# Measurements.net
KiCad netlist of a schematic drawn in Altium Designer
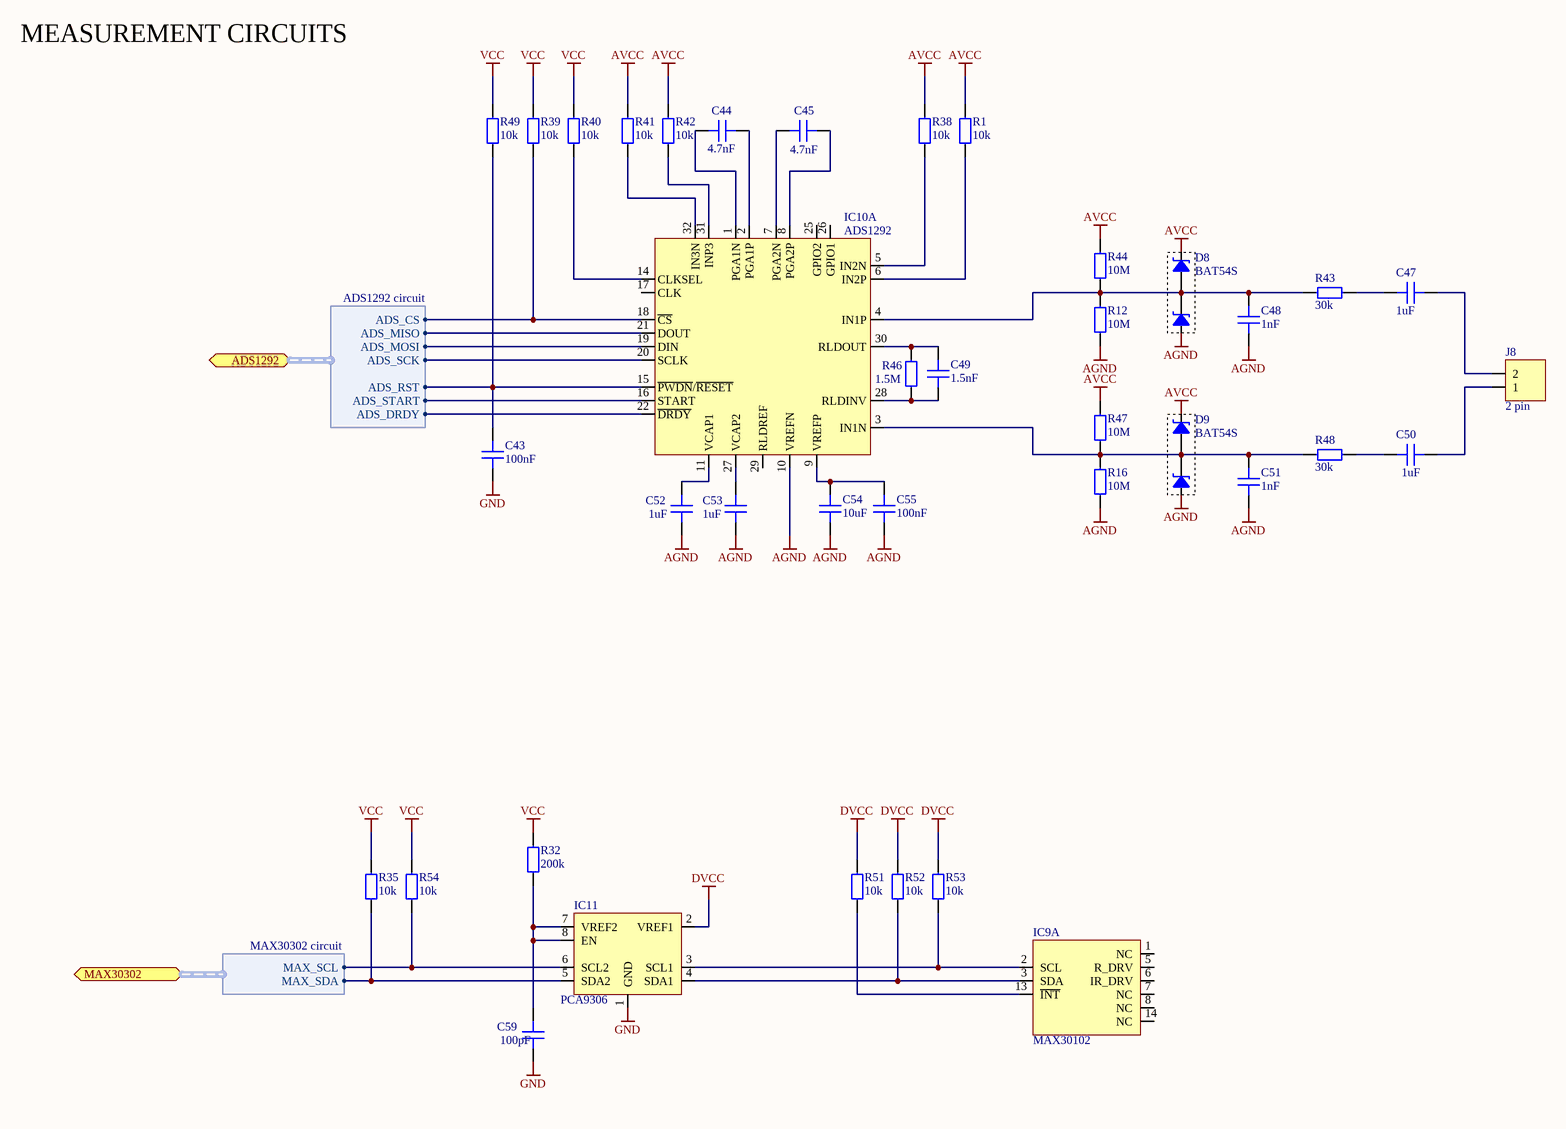
[diagram p0: Measurements.SchDoc]

(export (version "E")
  (design (tool "Eeschema 10.0.6"))
  (components
    (comp (ref "C43")
      (value "100nF")
      (footprint "CAP 0603")
      (description "SMT Capacitor")
      (libsource (lib "Passive") (part "Capacitor"))
    )
    (comp (ref "C44")
      (value "4.7nF")
      (footprint "CAP 0603")
      (description "SMT Capacitor")
      (libsource (lib "Passive") (part "Capacitor"))
    )
    (comp (ref "C45")
      (value "4.7nF")
      (footprint "CAP 0603")
      (description "SMT Capacitor")
      (libsource (lib "Passive") (part "Capacitor"))
    )
    (comp (ref "C47")
      (value "1uF")
      (footprint "CAP 0603")
      (description "SMT Capacitor")
      (libsource (lib "Passive") (part "Capacitor"))
    )
    (comp (ref "C48")
      (value "1nF")
      (footprint "CAP 0603")
      (description "SMT Capacitor")
      (libsource (lib "Passive") (part "Capacitor"))
    )
    (comp (ref "C49")
      (value "1.5nF")
      (footprint "CAP 0603")
      (description "SMT Capacitor")
      (libsource (lib "Passive") (part "Capacitor"))
    )
    (comp (ref "C50")
      (value "1uF")
      (footprint "CAP 0603")
      (description "SMT Capacitor")
      (libsource (lib "Passive") (part "Capacitor"))
    )
    (comp (ref "C51")
      (value "1nF")
      (footprint "CAP 0603")
      (description "SMT Capacitor")
      (libsource (lib "Passive") (part "Capacitor"))
    )
    (comp (ref "C52")
      (value "1uF")
      (footprint "CAP 0603")
      (description "SMT Capacitor")
      (libsource (lib "Passive") (part "Capacitor"))
    )
    (comp (ref "C53")
      (value "1uF")
      (footprint "CAP 0603")
      (description "SMT Capacitor")
      (libsource (lib "Passive") (part "Capacitor"))
    )
    (comp (ref "C54")
      (value "10uF")
      (footprint "CAP 0603")
      (description "SMT Capacitor")
      (libsource (lib "Passive") (part "Capacitor"))
    )
    (comp (ref "C55")
      (value "100nF")
      (footprint "CAP 0603")
      (description "SMT Capacitor")
      (libsource (lib "Passive") (part "Capacitor"))
    )
    (comp (ref "C59")
      (value "100pF")
      (footprint "CAP 0603")
      (description "SMT Capacitor")
      (libsource (lib "Passive") (part "Capacitor"))
    )
    (comp (ref "D8")
      (value "BAT54S")
      (footprint "SOT23")
      (description "Schottky barrier diodes")
      (libsource (lib "Diodes") (part "BAT54S"))
    )
    (comp (ref "D9")
      (value "BAT54S")
      (footprint "SOT23")
      (description "Schottky barrier diodes")
      (libsource (lib "Diodes") (part "BAT54S"))
    )
    (comp (ref "IC9")
      (value "MAX30102")
      (footprint "MAX30102")
      (description "Pulse Oximeter and Heart-Rate Sensor")
      (libsource (lib "IC") (part "MAX30102"))
    )
    (comp (ref "IC10")
      (value "ADS1292")
      (footprint "TQFP40")
      (description "ADS1292IRSMT Analog Front End - AFE Cmplt Lw Pwr Intgrtd AFE for ECG apps")
      (libsource (lib "IC") (part "ADS1292IRSMT"))
    )
    (comp (ref "IC11")
      (value "PCA9306")
      (footprint "SSOP8")
      (description "Dual Bidirectional I2C Bus and SMBus Voltage-Level Translator")
      (libsource (lib "IC") (part "PCA9306"))
    )
    (comp (ref "J8")
      (value "2 pin")
      (footprint "HDR 1x2 2.54")
      (description "2 pin header, male")
      (libsource (lib "Connectors") (part "2 pin"))
    )
    (comp (ref "R1")
      (value "10k")
      (footprint "RES 0603")
      (description "SMDResistor")
      (libsource (lib "Passive") (part "Resistor"))
    )
    (comp (ref "R12")
      (value "10M")
      (footprint "RES 0603")
      (description "SMDResistor")
      (libsource (lib "Passive") (part "Resistor"))
    )
    (comp (ref "R16")
      (value "10M")
      (footprint "RES 0603")
      (description "SMDResistor")
      (libsource (lib "Passive") (part "Resistor"))
    )
    (comp (ref "R32")
      (value "200k")
      (footprint "RES 0603")
      (description "SMDResistor")
      (libsource (lib "Passive") (part "Resistor"))
    )
    (comp (ref "R35")
      (value "10k")
      (footprint "RES 0603")
      (description "SMDResistor")
      (libsource (lib "Passive") (part "Resistor"))
    )
    (comp (ref "R38")
      (value "10k")
      (footprint "RES 0603")
      (description "SMDResistor")
      (libsource (lib "Passive") (part "Resistor"))
    )
    (comp (ref "R39")
      (value "10k")
      (footprint "RES 0603")
      (description "SMDResistor")
      (libsource (lib "Passive") (part "Resistor"))
    )
    (comp (ref "R40")
      (value "10k")
      (footprint "RES 0603")
      (description "SMDResistor")
      (libsource (lib "Passive") (part "Resistor"))
    )
    (comp (ref "R41")
      (value "10k")
      (footprint "RES 0603")
      (description "SMDResistor")
      (libsource (lib "Passive") (part "Resistor"))
    )
    (comp (ref "R42")
      (value "10k")
      (footprint "RES 0603")
      (description "SMDResistor")
      (libsource (lib "Passive") (part "Resistor"))
    )
    (comp (ref "R43")
      (value "30k")
      (footprint "RES 0603")
      (description "SMDResistor")
      (libsource (lib "Passive") (part "Resistor"))
    )
    (comp (ref "R44")
      (value "10M")
      (footprint "RES 0603")
      (description "SMDResistor")
      (libsource (lib "Passive") (part "Resistor"))
    )
    (comp (ref "R46")
      (value "1.5M")
      (footprint "RES 0603")
      (description "SMDResistor")
      (libsource (lib "Passive") (part "Resistor"))
    )
    (comp (ref "R47")
      (value "10M")
      (footprint "RES 0603")
      (description "SMDResistor")
      (libsource (lib "Passive") (part "Resistor"))
    )
    (comp (ref "R48")
      (value "30k")
      (footprint "RES 0603")
      (description "SMDResistor")
      (libsource (lib "Passive") (part "Resistor"))
    )
    (comp (ref "R49")
      (value "10k")
      (footprint "RES 0603")
      (description "SMDResistor")
      (libsource (lib "Passive") (part "Resistor"))
    )
    (comp (ref "R51")
      (value "10k")
      (footprint "RES 0603")
      (description "SMDResistor")
      (libsource (lib "Passive") (part "Resistor"))
    )
    (comp (ref "R52")
      (value "10k")
      (footprint "RES 0603")
      (description "SMDResistor")
      (libsource (lib "Passive") (part "Resistor"))
    )
    (comp (ref "R53")
      (value "10k")
      (footprint "RES 0603")
      (description "SMDResistor")
      (libsource (lib "Passive") (part "Resistor"))
    )
    (comp (ref "R54")
      (value "10k")
      (footprint "RES 0603")
      (description "SMDResistor")
      (libsource (lib "Passive") (part "Resistor"))
    )
  )
  (nets
    (net (code "4") (name "/ADS_CS") (class "Default")
      (node (ref "IC10") (pin "18") (pinfunction "~{CS}_18") (pintype "passive"))
      (node (ref "R39") (pin "1") (pinfunction "1_1") (pintype "passive"))
    )
    (net (code "5") (name "/ADS_DRDY") (class "Default")
      (node (ref "IC10") (pin "22") (pinfunction "~{DRDY}_22") (pintype "passive"))
    )
    (net (code "6") (name "/ADS_MISO") (class "Default")
      (node (ref "IC10") (pin "21") (pinfunction "DOUT_21") (pintype "passive"))
    )
    (net (code "7") (name "/ADS_MOSI") (class "Default")
      (node (ref "IC10") (pin "19") (pinfunction "DIN_19") (pintype "passive"))
    )
    (net (code "8") (name "/ADS_RST") (class "Default")
      (node (ref "C43") (pin "2") (pinfunction "2_2") (pintype "passive"))
      (node (ref "IC10") (pin "15") (pinfunction "~{PWDN}/~{RESET}_15") (pintype "passive"))
      (node (ref "R49") (pin "1") (pinfunction "1_1") (pintype "passive"))
    )
    (net (code "9") (name "/ADS_SCK") (class "Default")
      (node (ref "IC10") (pin "20") (pinfunction "SCLK_20") (pintype "passive"))
    )
    (net (code "10") (name "/ADS_START") (class "Default")
      (node (ref "IC10") (pin "16") (pinfunction "START_16") (pintype "passive"))
    )
    (net (code "11") (name "/MAX_SCL") (class "Default")
      (node (ref "IC11") (pin "6") (pinfunction "SCL2_6") (pintype "passive"))
      (node (ref "R54") (pin "1") (pinfunction "1_1") (pintype "passive"))
    )
    (net (code "12") (name "/MAX_SDA") (class "Default")
      (node (ref "IC11") (pin "5") (pinfunction "SDA2_5") (pintype "passive"))
      (node (ref "R35") (pin "1") (pinfunction "1_1") (pintype "passive"))
    )
    (net (code "15") (name "AGND") (class "Default")
      (node (ref "C48") (pin "1") (pinfunction "1_1") (pintype "passive"))
      (node (ref "C51") (pin "1") (pinfunction "1_1") (pintype "passive"))
      (node (ref "C52") (pin "1") (pinfunction "1_1") (pintype "passive"))
      (node (ref "C53") (pin "1") (pinfunction "1_1") (pintype "passive"))
      (node (ref "C54") (pin "1") (pinfunction "1_1") (pintype "passive"))
      (node (ref "C55") (pin "1") (pinfunction "1_1") (pintype "passive"))
      (node (ref "D8") (pin "1") (pinfunction "1_1") (pintype "passive"))
      (node (ref "D9") (pin "1") (pinfunction "1_1") (pintype "passive"))
      (node (ref "IC10") (pin "10") (pinfunction "VREFN_10") (pintype "passive"))
      (node (ref "R12") (pin "2") (pinfunction "2_2") (pintype "passive"))
      (node (ref "R16") (pin "2") (pinfunction "2_2") (pintype "passive"))
    )
    (net (code "16") (name "AVCC") (class "Default")
      (node (ref "D8") (pin "2") (pinfunction "2_2") (pintype "passive"))
      (node (ref "D9") (pin "2") (pinfunction "2_2") (pintype "passive"))
      (node (ref "R1") (pin "1") (pinfunction "1_1") (pintype "passive"))
      (node (ref "R38") (pin "1") (pinfunction "1_1") (pintype "passive"))
      (node (ref "R41") (pin "2") (pinfunction "2_2") (pintype "passive"))
      (node (ref "R42") (pin "2") (pinfunction "2_2") (pintype "passive"))
      (node (ref "R44") (pin "1") (pinfunction "1_1") (pintype "passive"))
      (node (ref "R47") (pin "1") (pinfunction "1_1") (pintype "passive"))
    )
    (net (code "17") (name "DVCC") (class "Default")
      (node (ref "IC11") (pin "2") (pinfunction "VREF1_2") (pintype "passive"))
      (node (ref "R51") (pin "2") (pinfunction "2_2") (pintype "passive"))
      (node (ref "R52") (pin "2") (pinfunction "2_2") (pintype "passive"))
      (node (ref "R53") (pin "2") (pinfunction "2_2") (pintype "passive"))
    )
    (net (code "18") (name "GND") (class "Default")
      (node (ref "C43") (pin "1") (pinfunction "1_1") (pintype "passive"))
      (node (ref "C59") (pin "1") (pinfunction "1_1") (pintype "passive"))
      (node (ref "IC11") (pin "1") (pinfunction "GND_1") (pintype "passive"))
    )
    (net (code "19") (name "Net-(C47-Pad1)") (class "Default")
      (node (ref "C47") (pin "1") (pinfunction "1_1") (pintype "passive"))
      (node (ref "J8") (pin "2") (pinfunction "2_2") (pintype "passive"))
    )
    (net (code "20") (name "Net-(C47-Pad2)") (class "Default")
      (node (ref "C47") (pin "2") (pinfunction "2_2") (pintype "passive"))
      (node (ref "R43") (pin "1") (pinfunction "1_1") (pintype "passive"))
    )
    (net (code "21") (name "Net-(C50-Pad1)") (class "Default")
      (node (ref "C50") (pin "1") (pinfunction "1_1") (pintype "passive"))
      (node (ref "J8") (pin "1") (pinfunction "1_1") (pintype "passive"))
    )
    (net (code "22") (name "Net-(C50-Pad2)") (class "Default")
      (node (ref "C50") (pin "2") (pinfunction "2_2") (pintype "passive"))
      (node (ref "R48") (pin "1") (pinfunction "1_1") (pintype "passive"))
    )
    (net (code "23") (name "Net-(IC9A-~{INT})") (class "Default")
      (node (ref "IC9") (pin "13") (pinfunction "~{INT}_13") (pintype "passive"))
      (node (ref "R51") (pin "1") (pinfunction "1_1") (pintype "passive"))
    )
    (net (code "24") (name "Net-(IC10A-CLKSEL)") (class "Default")
      (node (ref "IC10") (pin "14") (pinfunction "CLKSEL_14") (pintype "passive"))
      (node (ref "R40") (pin "1") (pinfunction "1_1") (pintype "passive"))
    )
    (net (code "25") (name "Net-(IC10A-IN1N)") (class "Default")
      (node (ref "C51") (pin "2") (pinfunction "2_2") (pintype "passive"))
      (node (ref "D9") (pin "3") (pinfunction "3_3") (pintype "passive"))
      (node (ref "IC10") (pin "3") (pinfunction "IN1N_3") (pintype "passive"))
      (node (ref "R16") (pin "1") (pinfunction "1_1") (pintype "passive"))
      (node (ref "R47") (pin "2") (pinfunction "2_2") (pintype "passive"))
      (node (ref "R48") (pin "2") (pinfunction "2_2") (pintype "passive"))
    )
    (net (code "26") (name "Net-(IC10A-IN1P)") (class "Default")
      (node (ref "C48") (pin "2") (pinfunction "2_2") (pintype "passive"))
      (node (ref "D8") (pin "3") (pinfunction "3_3") (pintype "passive"))
      (node (ref "IC10") (pin "4") (pinfunction "IN1P_4") (pintype "passive"))
      (node (ref "R12") (pin "1") (pinfunction "1_1") (pintype "passive"))
      (node (ref "R43") (pin "2") (pinfunction "2_2") (pintype "passive"))
      (node (ref "R44") (pin "2") (pinfunction "2_2") (pintype "passive"))
    )
    (net (code "27") (name "Net-(IC10A-IN2N)") (class "Default")
      (node (ref "IC10") (pin "5") (pinfunction "IN2N_5") (pintype "passive"))
      (node (ref "R38") (pin "2") (pinfunction "2_2") (pintype "passive"))
    )
    (net (code "28") (name "Net-(IC10A-IN2P)") (class "Default")
      (node (ref "IC10") (pin "6") (pinfunction "IN2P_6") (pintype "passive"))
      (node (ref "R1") (pin "2") (pinfunction "2_2") (pintype "passive"))
    )
    (net (code "29") (name "Net-(IC10A-IN3N)") (class "Default")
      (node (ref "IC10") (pin "32") (pinfunction "IN3N_32") (pintype "passive"))
      (node (ref "R41") (pin "1") (pinfunction "1_1") (pintype "passive"))
    )
    (net (code "30") (name "Net-(IC10A-INP3)") (class "Default")
      (node (ref "IC10") (pin "31") (pinfunction "INP3_31") (pintype "passive"))
      (node (ref "R42") (pin "1") (pinfunction "1_1") (pintype "passive"))
    )
    (net (code "31") (name "Net-(IC10A-PGA1N)") (class "Default")
      (node (ref "C44") (pin "1") (pinfunction "1_1") (pintype "passive"))
      (node (ref "IC10") (pin "1") (pinfunction "PGA1N_1") (pintype "passive"))
    )
    (net (code "32") (name "Net-(IC10A-PGA1P)") (class "Default")
      (node (ref "C44") (pin "2") (pinfunction "2_2") (pintype "passive"))
      (node (ref "IC10") (pin "2") (pinfunction "PGA1P_2") (pintype "passive"))
    )
    (net (code "33") (name "Net-(IC10A-PGA2N)") (class "Default")
      (node (ref "C45") (pin "1") (pinfunction "1_1") (pintype "passive"))
      (node (ref "IC10") (pin "7") (pinfunction "PGA2N_7") (pintype "passive"))
    )
    (net (code "34") (name "Net-(IC10A-PGA2P)") (class "Default")
      (node (ref "C45") (pin "2") (pinfunction "2_2") (pintype "passive"))
      (node (ref "IC10") (pin "8") (pinfunction "PGA2P_8") (pintype "passive"))
    )
    (net (code "35") (name "Net-(IC10A-RLDINV)") (class "Default")
      (node (ref "C49") (pin "1") (pinfunction "1_1") (pintype "passive"))
      (node (ref "IC10") (pin "28") (pinfunction "RLDINV_28") (pintype "passive"))
      (node (ref "R46") (pin "1") (pinfunction "1_1") (pintype "passive"))
    )
    (net (code "36") (name "Net-(IC10A-RLDOUT)") (class "Default")
      (node (ref "C49") (pin "2") (pinfunction "2_2") (pintype "passive"))
      (node (ref "IC10") (pin "30") (pinfunction "RLDOUT_30") (pintype "passive"))
      (node (ref "R46") (pin "2") (pinfunction "2_2") (pintype "passive"))
    )
    (net (code "37") (name "Net-(IC10A-VCAP1)") (class "Default")
      (node (ref "C52") (pin "2") (pinfunction "2_2") (pintype "passive"))
      (node (ref "IC10") (pin "11") (pinfunction "VCAP1_11") (pintype "passive"))
    )
    (net (code "38") (name "Net-(IC10A-VCAP2)") (class "Default")
      (node (ref "C53") (pin "2") (pinfunction "2_2") (pintype "passive"))
      (node (ref "IC10") (pin "27") (pinfunction "VCAP2_27") (pintype "passive"))
    )
    (net (code "39") (name "Net-(IC10A-VREFP)") (class "Default")
      (node (ref "C54") (pin "2") (pinfunction "2_2") (pintype "passive"))
      (node (ref "C55") (pin "2") (pinfunction "2_2") (pintype "passive"))
      (node (ref "IC10") (pin "9") (pinfunction "VREFP_9") (pintype "passive"))
    )
    (net (code "40") (name "Net-(IC11-EN)") (class "Default")
      (node (ref "C59") (pin "2") (pinfunction "2_2") (pintype "passive"))
      (node (ref "IC11") (pin "7") (pinfunction "VREF2_7") (pintype "passive"))
      (node (ref "IC11") (pin "8") (pinfunction "EN_8") (pintype "passive"))
      (node (ref "R32") (pin "1") (pinfunction "1_1") (pintype "passive"))
    )
    (net (code "41") (name "Net-(IC11-SCL1)") (class "Default")
      (node (ref "IC11") (pin "3") (pinfunction "SCL1_3") (pintype "passive"))
      (node (ref "IC9") (pin "2") (pinfunction "SCL_2") (pintype "passive"))
      (node (ref "R53") (pin "1") (pinfunction "1_1") (pintype "passive"))
    )
    (net (code "42") (name "Net-(IC11-SDA1)") (class "Default")
      (node (ref "IC11") (pin "4") (pinfunction "SDA1_4") (pintype "passive"))
      (node (ref "IC9") (pin "3") (pinfunction "SDA_3") (pintype "passive"))
      (node (ref "R52") (pin "1") (pinfunction "1_1") (pintype "passive"))
    )
    (net (code "43") (name "VCC") (class "Default")
      (node (ref "R32") (pin "2") (pinfunction "2_2") (pintype "passive"))
      (node (ref "R35") (pin "2") (pinfunction "2_2") (pintype "passive"))
      (node (ref "R39") (pin "2") (pinfunction "2_2") (pintype "passive"))
      (node (ref "R40") (pin "2") (pinfunction "2_2") (pintype "passive"))
      (node (ref "R49") (pin "2") (pinfunction "2_2") (pintype "passive"))
      (node (ref "R54") (pin "2") (pinfunction "2_2") (pintype "passive"))
    )
    (net (code "44") (name "unconnected-(IC9A-IR_DRV-Pad6)") (class "Default")
      (node (ref "IC9") (pin "6") (pinfunction "IR_DRV_6") (pintype "passive"))
    )
    (net (code "45") (name "unconnected-(IC9A-NC-Pad1)") (class "Default")
      (node (ref "IC9") (pin "1") (pinfunction "NC_1") (pintype "passive"))
    )
    (net (code "46") (name "unconnected-(IC9A-NC-Pad7)") (class "Default")
      (node (ref "IC9") (pin "7") (pinfunction "NC_7") (pintype "passive"))
    )
    (net (code "47") (name "unconnected-(IC9A-NC-Pad8)") (class "Default")
      (node (ref "IC9") (pin "8") (pinfunction "NC_8") (pintype "passive"))
    )
    (net (code "48") (name "unconnected-(IC9A-NC-Pad14)") (class "Default")
      (node (ref "IC9") (pin "14") (pinfunction "NC_14") (pintype "passive"))
    )
    (net (code "49") (name "unconnected-(IC9A-R_DRV-Pad5)") (class "Default")
      (node (ref "IC9") (pin "5") (pinfunction "R_DRV_5") (pintype "passive"))
    )
    (net (code "50") (name "unconnected-(IC10A-CLK-Pad17)") (class "Default")
      (node (ref "IC10") (pin "17") (pinfunction "CLK_17") (pintype "passive"))
    )
    (net (code "51") (name "unconnected-(IC10A-GPIO1-Pad26)") (class "Default")
      (node (ref "IC10") (pin "26") (pinfunction "GPIO1_26") (pintype "passive"))
    )
    (net (code "52") (name "unconnected-(IC10A-GPIO2-Pad25)") (class "Default")
      (node (ref "IC10") (pin "25") (pinfunction "GPIO2_25") (pintype "passive"))
    )
    (net (code "53") (name "unconnected-(IC10A-RLDREF-Pad29)") (class "Default")
      (node (ref "IC10") (pin "29") (pinfunction "RLDREF_29") (pintype "passive"))
    )
  )
)
